# DDR3L.net
KiCad netlist of a schematic drawn in Altium Designer
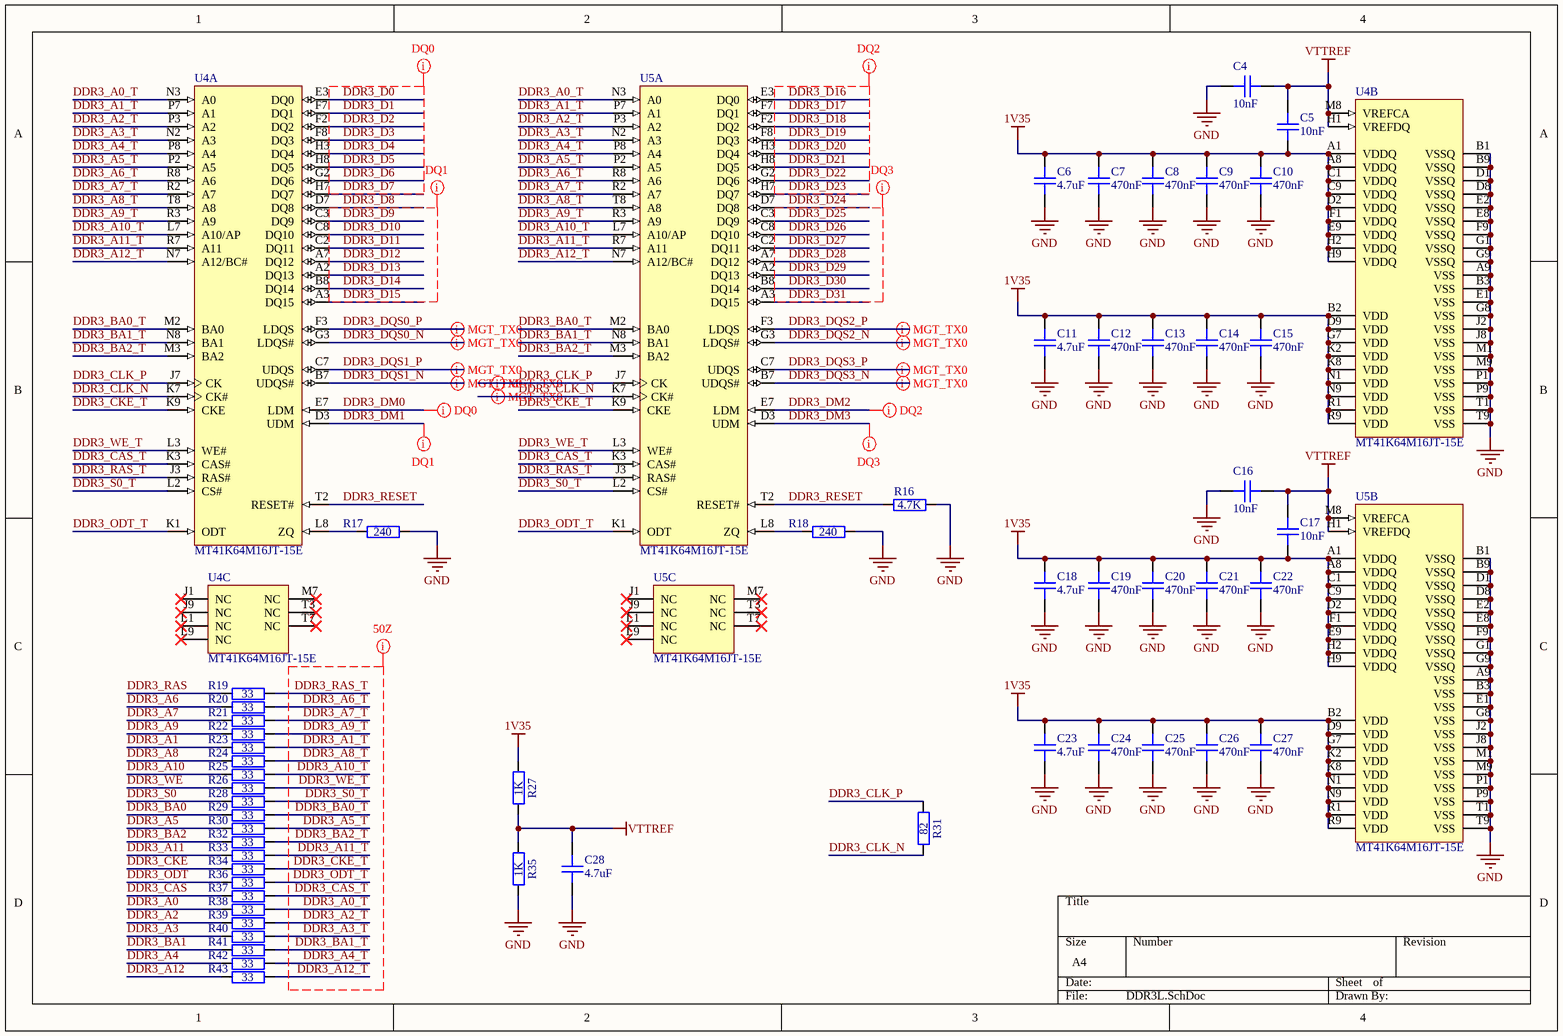
[diagram p0: DDR3L.SchDoc]

(export (version "E")
  (design (tool "Eeschema 10.0.6"))
  (components
    (comp (ref "C4")
      (value "10nF")
      (footprint "GEN_C_0402")
      (libsource (lib "DSO") (part "CAP 10nF 50V X7R 0402"))
    )
    (comp (ref "C5")
      (value "10nF")
      (footprint "GEN_C_0402")
      (libsource (lib "DSO") (part "CAP 10nF 50V X7R 0402"))
    )
    (comp (ref "C6")
      (value "4.7uF")
      (footprint "GEN_C_0402")
      (libsource (lib "DSO") (part "CAP 4.7uF 6.3V X5R 0402"))
    )
    (comp (ref "C7")
      (value "470nF")
      (footprint "GEN_C_0201")
      (libsource (lib "DSO") (part "CAP 470nF 6.3V X5R 0201"))
    )
    (comp (ref "C8")
      (value "470nF")
      (footprint "GEN_C_0201")
      (libsource (lib "DSO") (part "CAP 470nF 6.3V X5R 0201"))
    )
    (comp (ref "C9")
      (value "470nF")
      (footprint "GEN_C_0201")
      (libsource (lib "DSO") (part "CAP 470nF 6.3V X5R 0201"))
    )
    (comp (ref "C10")
      (value "470nF")
      (footprint "GEN_C_0201")
      (libsource (lib "DSO") (part "CAP 470nF 6.3V X5R 0201"))
    )
    (comp (ref "C11")
      (value "4.7uF")
      (footprint "GEN_C_0402")
      (libsource (lib "DSO") (part "CAP 4.7uF 6.3V X5R 0402"))
    )
    (comp (ref "C12")
      (value "470nF")
      (footprint "GEN_C_0201")
      (libsource (lib "DSO") (part "CAP 470nF 6.3V X5R 0201"))
    )
    (comp (ref "C13")
      (value "470nF")
      (footprint "GEN_C_0201")
      (libsource (lib "DSO") (part "CAP 470nF 6.3V X5R 0201"))
    )
    (comp (ref "C14")
      (value "470nF")
      (footprint "GEN_C_0201")
      (libsource (lib "DSO") (part "CAP 470nF 6.3V X5R 0201"))
    )
    (comp (ref "C15")
      (value "470nF")
      (footprint "GEN_C_0201")
      (libsource (lib "DSO") (part "CAP 470nF 6.3V X5R 0201"))
    )
    (comp (ref "C16")
      (value "10nF")
      (footprint "GEN_C_0402")
      (libsource (lib "DSO") (part "CAP 10nF 50V X7R 0402"))
    )
    (comp (ref "C17")
      (value "10nF")
      (footprint "GEN_C_0402")
      (libsource (lib "DSO") (part "CAP 10nF 50V X7R 0402"))
    )
    (comp (ref "C18")
      (value "4.7uF")
      (footprint "GEN_C_0402")
      (libsource (lib "DSO") (part "CAP 4.7uF 6.3V X5R 0402"))
    )
    (comp (ref "C19")
      (value "470nF")
      (footprint "GEN_C_0201")
      (libsource (lib "DSO") (part "CAP 470nF 6.3V X5R 0201"))
    )
    (comp (ref "C20")
      (value "470nF")
      (footprint "GEN_C_0201")
      (libsource (lib "DSO") (part "CAP 470nF 6.3V X5R 0201"))
    )
    (comp (ref "C21")
      (value "470nF")
      (footprint "GEN_C_0201")
      (libsource (lib "DSO") (part "CAP 470nF 6.3V X5R 0201"))
    )
    (comp (ref "C22")
      (value "470nF")
      (footprint "GEN_C_0201")
      (libsource (lib "DSO") (part "CAP 470nF 6.3V X5R 0201"))
    )
    (comp (ref "C23")
      (value "4.7uF")
      (footprint "GEN_C_0402")
      (libsource (lib "DSO") (part "CAP 4.7uF 6.3V X5R 0402"))
    )
    (comp (ref "C24")
      (value "470nF")
      (footprint "GEN_C_0201")
      (libsource (lib "DSO") (part "CAP 470nF 6.3V X5R 0201"))
    )
    (comp (ref "C25")
      (value "470nF")
      (footprint "GEN_C_0201")
      (libsource (lib "DSO") (part "CAP 470nF 6.3V X5R 0201"))
    )
    (comp (ref "C26")
      (value "470nF")
      (footprint "GEN_C_0201")
      (libsource (lib "DSO") (part "CAP 470nF 6.3V X5R 0201"))
    )
    (comp (ref "C27")
      (value "470nF")
      (footprint "GEN_C_0201")
      (libsource (lib "DSO") (part "CAP 470nF 6.3V X5R 0201"))
    )
    (comp (ref "C28")
      (value "4.7uF")
      (footprint "GEN_C_0402")
      (libsource (lib "DSO") (part "CAP 4.7uF 6.3V X5R 0402"))
    )
    (comp (ref "R16")
      (value "4.7K")
      (footprint "GEN_R_0402")
      (fields (field (name "TOLERANCE") "1%"))
      (libsource (lib "DSO") (part "RES 4.7K OHM 1% 1/10W 0402"))
    )
    (comp (ref "R17")
      (value "240")
      (footprint "GEN_R_0402")
      (fields (field (name "TOLERANCE") "1%"))
      (libsource (lib "DSO") (part "RES 240 OHM 1% 1/16W 0402"))
    )
    (comp (ref "R18")
      (value "240")
      (footprint "GEN_R_0402")
      (fields (field (name "TOLERANCE") "1%"))
      (libsource (lib "DSO") (part "RES 240 OHM 1% 1/16W 0402"))
    )
    (comp (ref "R19")
      (value "33")
      (footprint "GEN_R_0201")
      (fields (field (name "TOLERANCE") "1%"))
      (libsource (lib "DSO") (part "RES 33 OHM 1% 1/20W 0201"))
    )
    (comp (ref "R20")
      (value "33")
      (footprint "GEN_R_0201")
      (fields (field (name "TOLERANCE") "1%"))
      (libsource (lib "DSO") (part "RES 33 OHM 1% 1/20W 0201"))
    )
    (comp (ref "R21")
      (value "33")
      (footprint "GEN_R_0201")
      (fields (field (name "TOLERANCE") "1%"))
      (libsource (lib "DSO") (part "RES 33 OHM 1% 1/20W 0201"))
    )
    (comp (ref "R22")
      (value "33")
      (footprint "GEN_R_0201")
      (fields (field (name "TOLERANCE") "1%"))
      (libsource (lib "DSO") (part "RES 33 OHM 1% 1/20W 0201"))
    )
    (comp (ref "R23")
      (value "33")
      (footprint "GEN_R_0201")
      (fields (field (name "TOLERANCE") "1%"))
      (libsource (lib "DSO") (part "RES 33 OHM 1% 1/20W 0201"))
    )
    (comp (ref "R24")
      (value "33")
      (footprint "GEN_R_0201")
      (fields (field (name "TOLERANCE") "1%"))
      (libsource (lib "DSO") (part "RES 33 OHM 1% 1/20W 0201"))
    )
    (comp (ref "R25")
      (value "33")
      (footprint "GEN_R_0201")
      (fields (field (name "TOLERANCE") "1%"))
      (libsource (lib "DSO") (part "RES 33 OHM 1% 1/20W 0201"))
    )
    (comp (ref "R26")
      (value "33")
      (footprint "GEN_R_0201")
      (fields (field (name "TOLERANCE") "1%"))
      (libsource (lib "DSO") (part "RES 33 OHM 1% 1/20W 0201"))
    )
    (comp (ref "R27")
      (value "1K")
      (footprint "GEN_R_0402")
      (fields (field (name "TOLERANCE") "1%"))
      (libsource (lib "DSO") (part "RES 1K OHM 1% 1/10W 0402"))
    )
    (comp (ref "R28")
      (value "33")
      (footprint "GEN_R_0201")
      (fields (field (name "TOLERANCE") "1%"))
      (libsource (lib "DSO") (part "RES 33 OHM 1% 1/20W 0201"))
    )
    (comp (ref "R29")
      (value "33")
      (footprint "GEN_R_0201")
      (fields (field (name "TOLERANCE") "1%"))
      (libsource (lib "DSO") (part "RES 33 OHM 1% 1/20W 0201"))
    )
    (comp (ref "R30")
      (value "33")
      (footprint "GEN_R_0201")
      (fields (field (name "TOLERANCE") "1%"))
      (libsource (lib "DSO") (part "RES 33 OHM 1% 1/20W 0201"))
    )
    (comp (ref "R31")
      (value "82")
      (footprint "GEN_R_0402")
      (fields (field (name "TOLERANCE") "1%"))
      (libsource (lib "DSO") (part "RES 82 OHM 1% 1/16W 0402"))
    )
    (comp (ref "R32")
      (value "33")
      (footprint "GEN_R_0201")
      (fields (field (name "TOLERANCE") "1%"))
      (libsource (lib "DSO") (part "RES 33 OHM 1% 1/20W 0201"))
    )
    (comp (ref "R33")
      (value "33")
      (footprint "GEN_R_0201")
      (fields (field (name "TOLERANCE") "1%"))
      (libsource (lib "DSO") (part "RES 33 OHM 1% 1/20W 0201"))
    )
    (comp (ref "R34")
      (value "33")
      (footprint "GEN_R_0201")
      (fields (field (name "TOLERANCE") "1%"))
      (libsource (lib "DSO") (part "RES 33 OHM 1% 1/20W 0201"))
    )
    (comp (ref "R35")
      (value "1K")
      (footprint "GEN_R_0402")
      (fields (field (name "TOLERANCE") "1%"))
      (libsource (lib "DSO") (part "RES 1K OHM 1% 1/10W 0402"))
    )
    (comp (ref "R36")
      (value "33")
      (footprint "GEN_R_0201")
      (fields (field (name "TOLERANCE") "1%"))
      (libsource (lib "DSO") (part "RES 33 OHM 1% 1/20W 0201"))
    )
    (comp (ref "R37")
      (value "33")
      (footprint "GEN_R_0201")
      (fields (field (name "TOLERANCE") "1%"))
      (libsource (lib "DSO") (part "RES 33 OHM 1% 1/20W 0201"))
    )
    (comp (ref "R38")
      (value "33")
      (footprint "GEN_R_0201")
      (fields (field (name "TOLERANCE") "1%"))
      (libsource (lib "DSO") (part "RES 33 OHM 1% 1/20W 0201"))
    )
    (comp (ref "R39")
      (value "33")
      (footprint "GEN_R_0201")
      (fields (field (name "TOLERANCE") "1%"))
      (libsource (lib "DSO") (part "RES 33 OHM 1% 1/20W 0201"))
    )
    (comp (ref "R40")
      (value "33")
      (footprint "GEN_R_0201")
      (fields (field (name "TOLERANCE") "1%"))
      (libsource (lib "DSO") (part "RES 33 OHM 1% 1/20W 0201"))
    )
    (comp (ref "R41")
      (value "33")
      (footprint "GEN_R_0201")
      (fields (field (name "TOLERANCE") "1%"))
      (libsource (lib "DSO") (part "RES 33 OHM 1% 1/20W 0201"))
    )
    (comp (ref "R42")
      (value "33")
      (footprint "GEN_R_0201")
      (fields (field (name "TOLERANCE") "1%"))
      (libsource (lib "DSO") (part "RES 33 OHM 1% 1/20W 0201"))
    )
    (comp (ref "R43")
      (value "33")
      (footprint "GEN_R_0201")
      (fields (field (name "TOLERANCE") "1%"))
      (libsource (lib "DSO") (part "RES 33 OHM 1% 1/20W 0201"))
    )
    (comp (ref "U4")
      (value "MT41K64M16JT-15E")
      (footprint "MICT-JT-96")
      (description "1Gb DDR3-1333 SDRAM, 64Mb x 16, 1.5ns, 1.35V, 0 to 95 degC, 96-Ball FBGA, Pb-Free")
      (fields (field (name "VOLTAGE") "1.35V") (field (name "MANUFACTURER") "Micron"))
      (libsource (lib "Micron Memory DDR3 SDRAM") (part "MT41K64M16JT-15E"))
    )
    (comp (ref "U5")
      (value "MT41K64M16JT-15E")
      (footprint "MICT-JT-96")
      (description "1Gb DDR3-1333 SDRAM, 64Mb x 16, 1.5ns, 1.35V, 0 to 95 degC, 96-Ball FBGA, Pb-Free")
      (fields (field (name "VOLTAGE") "1.35V") (field (name "MANUFACTURER") "Micron"))
      (libsource (lib "Micron Memory DDR3 SDRAM") (part "MT41K64M16JT-15E"))
    )
  )
  (nets
    (net (code "1") (name "/DDR3_A0") (class "Default")
      (node (ref "R38") (pin "1") (pinfunction "1_1") (pintype "passive"))
    )
    (net (code "2") (name "/DDR3_A0_T") (class "Default")
      (node (ref "R38") (pin "2") (pinfunction "2_2") (pintype "passive"))
      (node (ref "U4") (pin "N3") (pinfunction "A0_N3") (pintype "input"))
      (node (ref "U5") (pin "N3") (pinfunction "A0_N3") (pintype "input"))
    )
    (net (code "3") (name "/DDR3_A1") (class "Default")
      (node (ref "R23") (pin "1") (pinfunction "1_1") (pintype "passive"))
    )
    (net (code "4") (name "/DDR3_A1_T") (class "Default")
      (node (ref "R23") (pin "2") (pinfunction "2_2") (pintype "passive"))
      (node (ref "U4") (pin "P7") (pinfunction "A1_P7") (pintype "input"))
      (node (ref "U5") (pin "P7") (pinfunction "A1_P7") (pintype "input"))
    )
    (net (code "5") (name "/DDR3_A2") (class "Default")
      (node (ref "R39") (pin "1") (pinfunction "1_1") (pintype "passive"))
    )
    (net (code "6") (name "/DDR3_A2_T") (class "Default")
      (node (ref "R39") (pin "2") (pinfunction "2_2") (pintype "passive"))
      (node (ref "U4") (pin "P3") (pinfunction "A2_P3") (pintype "input"))
      (node (ref "U5") (pin "P3") (pinfunction "A2_P3") (pintype "input"))
    )
    (net (code "7") (name "/DDR3_A3") (class "Default")
      (node (ref "R40") (pin "1") (pinfunction "1_1") (pintype "passive"))
    )
    (net (code "8") (name "/DDR3_A3_T") (class "Default")
      (node (ref "R40") (pin "2") (pinfunction "2_2") (pintype "passive"))
      (node (ref "U4") (pin "N2") (pinfunction "A3_N2") (pintype "input"))
      (node (ref "U5") (pin "N2") (pinfunction "A3_N2") (pintype "input"))
    )
    (net (code "9") (name "/DDR3_A4") (class "Default")
      (node (ref "R42") (pin "1") (pinfunction "1_1") (pintype "passive"))
    )
    (net (code "10") (name "/DDR3_A4_T") (class "Default")
      (node (ref "R42") (pin "2") (pinfunction "2_2") (pintype "passive"))
      (node (ref "U4") (pin "P8") (pinfunction "A4_P8") (pintype "input"))
      (node (ref "U5") (pin "P8") (pinfunction "A4_P8") (pintype "input"))
    )
    (net (code "11") (name "/DDR3_A5") (class "Default")
      (node (ref "R30") (pin "1") (pinfunction "1_1") (pintype "passive"))
    )
    (net (code "12") (name "/DDR3_A5_T") (class "Default")
      (node (ref "R30") (pin "2") (pinfunction "2_2") (pintype "passive"))
      (node (ref "U4") (pin "P2") (pinfunction "A5_P2") (pintype "input"))
      (node (ref "U5") (pin "P2") (pinfunction "A5_P2") (pintype "input"))
    )
    (net (code "13") (name "/DDR3_A6") (class "Default")
      (node (ref "R20") (pin "1") (pinfunction "1_1") (pintype "passive"))
    )
    (net (code "14") (name "/DDR3_A6_T") (class "Default")
      (node (ref "R20") (pin "2") (pinfunction "2_2") (pintype "passive"))
      (node (ref "U4") (pin "R8") (pinfunction "A6_R8") (pintype "input"))
      (node (ref "U5") (pin "R8") (pinfunction "A6_R8") (pintype "input"))
    )
    (net (code "15") (name "/DDR3_A7") (class "Default")
      (node (ref "R21") (pin "1") (pinfunction "1_1") (pintype "passive"))
    )
    (net (code "16") (name "/DDR3_A7_T") (class "Default")
      (node (ref "R21") (pin "2") (pinfunction "2_2") (pintype "passive"))
      (node (ref "U4") (pin "R2") (pinfunction "A7_R2") (pintype "input"))
      (node (ref "U5") (pin "R2") (pinfunction "A7_R2") (pintype "input"))
    )
    (net (code "17") (name "/DDR3_A8") (class "Default")
      (node (ref "R24") (pin "1") (pinfunction "1_1") (pintype "passive"))
    )
    (net (code "18") (name "/DDR3_A8_T") (class "Default")
      (node (ref "R24") (pin "2") (pinfunction "2_2") (pintype "passive"))
      (node (ref "U4") (pin "T8") (pinfunction "A8_T8") (pintype "input"))
      (node (ref "U5") (pin "T8") (pinfunction "A8_T8") (pintype "input"))
    )
    (net (code "19") (name "/DDR3_A9") (class "Default")
      (node (ref "R22") (pin "1") (pinfunction "1_1") (pintype "passive"))
    )
    (net (code "20") (name "/DDR3_A9_T") (class "Default")
      (node (ref "R22") (pin "2") (pinfunction "2_2") (pintype "passive"))
      (node (ref "U4") (pin "R3") (pinfunction "A9_R3") (pintype "input"))
      (node (ref "U5") (pin "R3") (pinfunction "A9_R3") (pintype "input"))
    )
    (net (code "21") (name "/DDR3_A10") (class "Default")
      (node (ref "R25") (pin "1") (pinfunction "1_1") (pintype "passive"))
    )
    (net (code "22") (name "/DDR3_A10_T") (class "Default")
      (node (ref "R25") (pin "2") (pinfunction "2_2") (pintype "passive"))
      (node (ref "U4") (pin "L7") (pinfunction "A10/AP_L7") (pintype "input"))
      (node (ref "U5") (pin "L7") (pinfunction "A10/AP_L7") (pintype "input"))
    )
    (net (code "23") (name "/DDR3_A11") (class "Default")
      (node (ref "R33") (pin "1") (pinfunction "1_1") (pintype "passive"))
    )
    (net (code "24") (name "/DDR3_A11_T") (class "Default")
      (node (ref "R33") (pin "2") (pinfunction "2_2") (pintype "passive"))
      (node (ref "U4") (pin "R7") (pinfunction "A11_R7") (pintype "input"))
      (node (ref "U5") (pin "R7") (pinfunction "A11_R7") (pintype "input"))
    )
    (net (code "25") (name "/DDR3_A12") (class "Default")
      (node (ref "R43") (pin "1") (pinfunction "1_1") (pintype "passive"))
    )
    (net (code "26") (name "/DDR3_A12_T") (class "Default")
      (node (ref "R43") (pin "2") (pinfunction "2_2") (pintype "passive"))
      (node (ref "U4") (pin "N7") (pinfunction "A12/BC#_N7") (pintype "input"))
      (node (ref "U5") (pin "N7") (pinfunction "A12/BC#_N7") (pintype "input"))
    )
    (net (code "27") (name "/DDR3_BA0") (class "Default")
      (node (ref "R29") (pin "1") (pinfunction "1_1") (pintype "passive"))
    )
    (net (code "28") (name "/DDR3_BA0_T") (class "Default")
      (node (ref "R29") (pin "2") (pinfunction "2_2") (pintype "passive"))
      (node (ref "U4") (pin "M2") (pinfunction "BA0_M2") (pintype "input"))
      (node (ref "U5") (pin "M2") (pinfunction "BA0_M2") (pintype "input"))
    )
    (net (code "29") (name "/DDR3_BA1") (class "Default")
      (node (ref "R41") (pin "1") (pinfunction "1_1") (pintype "passive"))
    )
    (net (code "30") (name "/DDR3_BA1_T") (class "Default")
      (node (ref "R41") (pin "2") (pinfunction "2_2") (pintype "passive"))
      (node (ref "U4") (pin "N8") (pinfunction "BA1_N8") (pintype "input"))
      (node (ref "U5") (pin "N8") (pinfunction "BA1_N8") (pintype "input"))
    )
    (net (code "31") (name "/DDR3_BA2") (class "Default")
      (node (ref "R32") (pin "1") (pinfunction "1_1") (pintype "passive"))
    )
    (net (code "32") (name "/DDR3_BA2_T") (class "Default")
      (node (ref "R32") (pin "2") (pinfunction "2_2") (pintype "passive"))
      (node (ref "U4") (pin "M3") (pinfunction "BA2_M3") (pintype "input"))
      (node (ref "U5") (pin "M3") (pinfunction "BA2_M3") (pintype "input"))
    )
    (net (code "33") (name "/DDR3_CAS") (class "Default")
      (node (ref "R37") (pin "1") (pinfunction "1_1") (pintype "passive"))
    )
    (net (code "34") (name "/DDR3_CAS_T") (class "Default")
      (node (ref "R37") (pin "2") (pinfunction "2_2") (pintype "passive"))
      (node (ref "U4") (pin "K3") (pinfunction "CAS#_K3") (pintype "input"))
      (node (ref "U5") (pin "K3") (pinfunction "CAS#_K3") (pintype "input"))
    )
    (net (code "35") (name "/DDR3_CKE") (class "Default")
      (node (ref "R34") (pin "1") (pinfunction "1_1") (pintype "passive"))
    )
    (net (code "36") (name "/DDR3_CKE_T") (class "Default")
      (node (ref "R34") (pin "2") (pinfunction "2_2") (pintype "passive"))
      (node (ref "U4") (pin "K9") (pinfunction "CKE_K9") (pintype "input"))
      (node (ref "U5") (pin "K9") (pinfunction "CKE_K9") (pintype "input"))
    )
    (net (code "37") (name "/DDR3_CLK_N") (class "Default")
      (node (ref "R31") (pin "1") (pinfunction "1_1") (pintype "passive"))
      (node (ref "U4") (pin "K7") (pinfunction "CK#_K7") (pintype "input"))
      (node (ref "U5") (pin "K7") (pinfunction "CK#_K7") (pintype "input"))
    )
    (net (code "38") (name "/DDR3_CLK_P") (class "Default")
      (node (ref "R31") (pin "2") (pinfunction "2_2") (pintype "passive"))
      (node (ref "U4") (pin "J7") (pinfunction "CK_J7") (pintype "input"))
      (node (ref "U5") (pin "J7") (pinfunction "CK_J7") (pintype "input"))
    )
    (net (code "39") (name "/DDR3_D0") (class "Default")
      (node (ref "U4") (pin "E3") (pinfunction "DQ0_E3") (pintype "bidirectional"))
    )
    (net (code "40") (name "/DDR3_D1") (class "Default")
      (node (ref "U4") (pin "F7") (pinfunction "DQ1_F7") (pintype "bidirectional"))
    )
    (net (code "41") (name "/DDR3_D2") (class "Default")
      (node (ref "U4") (pin "F2") (pinfunction "DQ2_F2") (pintype "bidirectional"))
    )
    (net (code "42") (name "/DDR3_D3") (class "Default")
      (node (ref "U4") (pin "F8") (pinfunction "DQ3_F8") (pintype "bidirectional"))
    )
    (net (code "43") (name "/DDR3_D4") (class "Default")
      (node (ref "U4") (pin "H3") (pinfunction "DQ4_H3") (pintype "bidirectional"))
    )
    (net (code "44") (name "/DDR3_D5") (class "Default")
      (node (ref "U4") (pin "H8") (pinfunction "DQ5_H8") (pintype "bidirectional"))
    )
    (net (code "45") (name "/DDR3_D6") (class "Default")
      (node (ref "U4") (pin "G2") (pinfunction "DQ6_G2") (pintype "bidirectional"))
    )
    (net (code "46") (name "/DDR3_D7") (class "Default")
      (node (ref "U4") (pin "H7") (pinfunction "DQ7_H7") (pintype "bidirectional"))
    )
    (net (code "47") (name "/DDR3_D8") (class "Default")
      (node (ref "U4") (pin "D7") (pinfunction "DQ8_D7") (pintype "bidirectional"))
    )
    (net (code "48") (name "/DDR3_D9") (class "Default")
      (node (ref "U4") (pin "C3") (pinfunction "DQ9_C3") (pintype "bidirectional"))
    )
    (net (code "49") (name "/DDR3_D10") (class "Default")
      (node (ref "U4") (pin "C8") (pinfunction "DQ10_C8") (pintype "bidirectional"))
    )
    (net (code "50") (name "/DDR3_D11") (class "Default")
      (node (ref "U4") (pin "C2") (pinfunction "DQ11_C2") (pintype "bidirectional"))
    )
    (net (code "51") (name "/DDR3_D12") (class "Default")
      (node (ref "U4") (pin "A7") (pinfunction "DQ12_A7") (pintype "bidirectional"))
    )
    (net (code "52") (name "/DDR3_D13") (class "Default")
      (node (ref "U4") (pin "A2") (pinfunction "DQ13_A2") (pintype "bidirectional"))
    )
    (net (code "53") (name "/DDR3_D14") (class "Default")
      (node (ref "U4") (pin "B8") (pinfunction "DQ14_B8") (pintype "bidirectional"))
    )
    (net (code "54") (name "/DDR3_D15") (class "Default")
      (node (ref "U4") (pin "A3") (pinfunction "DQ15_A3") (pintype "bidirectional"))
    )
    (net (code "55") (name "/DDR3_D16") (class "Default")
      (node (ref "U5") (pin "E3") (pinfunction "DQ0_E3") (pintype "bidirectional"))
    )
    (net (code "56") (name "/DDR3_D17") (class "Default")
      (node (ref "U5") (pin "F7") (pinfunction "DQ1_F7") (pintype "bidirectional"))
    )
    (net (code "57") (name "/DDR3_D18") (class "Default")
      (node (ref "U5") (pin "F2") (pinfunction "DQ2_F2") (pintype "bidirectional"))
    )
    (net (code "58") (name "/DDR3_D19") (class "Default")
      (node (ref "U5") (pin "F8") (pinfunction "DQ3_F8") (pintype "bidirectional"))
    )
    (net (code "59") (name "/DDR3_D20") (class "Default")
      (node (ref "U5") (pin "H3") (pinfunction "DQ4_H3") (pintype "bidirectional"))
    )
    (net (code "60") (name "/DDR3_D21") (class "Default")
      (node (ref "U5") (pin "H8") (pinfunction "DQ5_H8") (pintype "bidirectional"))
    )
    (net (code "61") (name "/DDR3_D22") (class "Default")
      (node (ref "U5") (pin "G2") (pinfunction "DQ6_G2") (pintype "bidirectional"))
    )
    (net (code "62") (name "/DDR3_D23") (class "Default")
      (node (ref "U5") (pin "H7") (pinfunction "DQ7_H7") (pintype "bidirectional"))
    )
    (net (code "63") (name "/DDR3_D24") (class "Default")
      (node (ref "U5") (pin "D7") (pinfunction "DQ8_D7") (pintype "bidirectional"))
    )
    (net (code "64") (name "/DDR3_D25") (class "Default")
      (node (ref "U5") (pin "C3") (pinfunction "DQ9_C3") (pintype "bidirectional"))
    )
    (net (code "65") (name "/DDR3_D26") (class "Default")
      (node (ref "U5") (pin "C8") (pinfunction "DQ10_C8") (pintype "bidirectional"))
    )
    (net (code "66") (name "/DDR3_D27") (class "Default")
      (node (ref "U5") (pin "C2") (pinfunction "DQ11_C2") (pintype "bidirectional"))
    )
    (net (code "67") (name "/DDR3_D28") (class "Default")
      (node (ref "U5") (pin "A7") (pinfunction "DQ12_A7") (pintype "bidirectional"))
    )
    (net (code "68") (name "/DDR3_D29") (class "Default")
      (node (ref "U5") (pin "A2") (pinfunction "DQ13_A2") (pintype "bidirectional"))
    )
    (net (code "69") (name "/DDR3_D30") (class "Default")
      (node (ref "U5") (pin "B8") (pinfunction "DQ14_B8") (pintype "bidirectional"))
    )
    (net (code "70") (name "/DDR3_D31") (class "Default")
      (node (ref "U5") (pin "A3") (pinfunction "DQ15_A3") (pintype "bidirectional"))
    )
    (net (code "71") (name "/DDR3_DM0") (class "Default")
      (node (ref "U4") (pin "E7") (pinfunction "LDM_E7") (pintype "input"))
    )
    (net (code "72") (name "/DDR3_DM1") (class "Default")
      (node (ref "U4") (pin "D3") (pinfunction "UDM_D3") (pintype "input"))
    )
    (net (code "73") (name "/DDR3_DM2") (class "Default")
      (node (ref "U5") (pin "E7") (pinfunction "LDM_E7") (pintype "input"))
    )
    (net (code "74") (name "/DDR3_DM3") (class "Default")
      (node (ref "U5") (pin "D3") (pinfunction "UDM_D3") (pintype "input"))
    )
    (net (code "75") (name "/DDR3_DQS0_N") (class "Default")
      (node (ref "U4") (pin "G3") (pinfunction "LDQS#_G3") (pintype "bidirectional"))
    )
    (net (code "76") (name "/DDR3_DQS0_P") (class "Default")
      (node (ref "U4") (pin "F3") (pinfunction "LDQS_F3") (pintype "bidirectional"))
    )
    (net (code "77") (name "/DDR3_DQS1_N") (class "Default")
      (node (ref "U4") (pin "B7") (pinfunction "UDQS#_B7") (pintype "bidirectional"))
    )
    (net (code "78") (name "/DDR3_DQS1_P") (class "Default")
      (node (ref "U4") (pin "C7") (pinfunction "UDQS_C7") (pintype "bidirectional"))
    )
    (net (code "79") (name "/DDR3_DQS2_N") (class "Default")
      (node (ref "U5") (pin "G3") (pinfunction "LDQS#_G3") (pintype "bidirectional"))
    )
    (net (code "80") (name "/DDR3_DQS2_P") (class "Default")
      (node (ref "U5") (pin "F3") (pinfunction "LDQS_F3") (pintype "bidirectional"))
    )
    (net (code "81") (name "/DDR3_DQS3_N") (class "Default")
      (node (ref "U5") (pin "B7") (pinfunction "UDQS#_B7") (pintype "bidirectional"))
    )
    (net (code "82") (name "/DDR3_DQS3_P") (class "Default")
      (node (ref "U5") (pin "C7") (pinfunction "UDQS_C7") (pintype "bidirectional"))
    )
    (net (code "83") (name "/DDR3_ODT") (class "Default")
      (node (ref "R36") (pin "1") (pinfunction "1_1") (pintype "passive"))
    )
    (net (code "84") (name "/DDR3_ODT_T") (class "Default")
      (node (ref "R36") (pin "2") (pinfunction "2_2") (pintype "passive"))
      (node (ref "U4") (pin "K1") (pinfunction "ODT_K1") (pintype "input"))
      (node (ref "U5") (pin "K1") (pinfunction "ODT_K1") (pintype "input"))
    )
    (net (code "85") (name "/DDR3_RAS") (class "Default")
      (node (ref "R19") (pin "1") (pinfunction "1_1") (pintype "passive"))
    )
    (net (code "86") (name "/DDR3_RAS_T") (class "Default")
      (node (ref "R19") (pin "2") (pinfunction "2_2") (pintype "passive"))
      (node (ref "U4") (pin "J3") (pinfunction "RAS#_J3") (pintype "input"))
      (node (ref "U5") (pin "J3") (pinfunction "RAS#_J3") (pintype "input"))
    )
    (net (code "87") (name "/DDR3_RESET") (class "Default")
      (node (ref "R16") (pin "1") (pinfunction "1_1") (pintype "passive"))
      (node (ref "U4") (pin "T2") (pinfunction "RESET#_T2") (pintype "input"))
      (node (ref "U5") (pin "T2") (pinfunction "RESET#_T2") (pintype "input"))
    )
    (net (code "88") (name "/DDR3_S0") (class "Default")
      (node (ref "R28") (pin "1") (pinfunction "1_1") (pintype "passive"))
    )
    (net (code "89") (name "/DDR3_S0_T") (class "Default")
      (node (ref "R28") (pin "2") (pinfunction "2_2") (pintype "passive"))
      (node (ref "U4") (pin "L2") (pinfunction "CS#_L2") (pintype "input"))
      (node (ref "U5") (pin "L2") (pinfunction "CS#_L2") (pintype "input"))
    )
    (net (code "90") (name "/DDR3_WE") (class "Default")
      (node (ref "R26") (pin "1") (pinfunction "1_1") (pintype "passive"))
    )
    (net (code "91") (name "/DDR3_WE_T") (class "Default")
      (node (ref "R26") (pin "2") (pinfunction "2_2") (pintype "passive"))
      (node (ref "U4") (pin "L3") (pinfunction "WE#_L3") (pintype "input"))
      (node (ref "U5") (pin "L3") (pinfunction "WE#_L3") (pintype "input"))
    )
    (net (code "92") (name "1V35") (class "Default")
      (node (ref "C10") (pin "2") (pinfunction "2_2") (pintype "passive"))
      (node (ref "C11") (pin "2") (pinfunction "2_2") (pintype "passive"))
      (node (ref "C12") (pin "2") (pinfunction "2_2") (pintype "passive"))
      (node (ref "C13") (pin "2") (pinfunction "2_2") (pintype "passive"))
      (node (ref "C14") (pin "2") (pinfunction "2_2") (pintype "passive"))
      (node (ref "C15") (pin "2") (pinfunction "2_2") (pintype "passive"))
      (node (ref "C17") (pin "2") (pinfunction "2_2") (pintype "passive"))
      (node (ref "C18") (pin "2") (pinfunction "2_2") (pintype "passive"))
      (node (ref "C19") (pin "2") (pinfunction "2_2") (pintype "passive"))
      (node (ref "C20") (pin "2") (pinfunction "2_2") (pintype "passive"))
      (node (ref "C21") (pin "2") (pinfunction "2_2") (pintype "passive"))
      (node (ref "C22") (pin "2") (pinfunction "2_2") (pintype "passive"))
      (node (ref "C23") (pin "2") (pinfunction "2_2") (pintype "passive"))
      (node (ref "C24") (pin "2") (pinfunction "2_2") (pintype "passive"))
      (node (ref "C25") (pin "2") (pinfunction "2_2") (pintype "passive"))
      (node (ref "C26") (pin "2") (pinfunction "2_2") (pintype "passive"))
      (node (ref "C27") (pin "2") (pinfunction "2_2") (pintype "passive"))
      (node (ref "C5") (pin "2") (pinfunction "2_2") (pintype "passive"))
      (node (ref "C6") (pin "2") (pinfunction "2_2") (pintype "passive"))
      (node (ref "C7") (pin "2") (pinfunction "2_2") (pintype "passive"))
      (node (ref "C8") (pin "2") (pinfunction "2_2") (pintype "passive"))
      (node (ref "C9") (pin "2") (pinfunction "2_2") (pintype "passive"))
      (node (ref "R27") (pin "2") (pinfunction "2_2") (pintype "passive"))
      (node (ref "U4") (pin "A1") (pinfunction "VDDQ_A1") (pintype "power_in"))
      (node (ref "U4") (pin "A8") (pinfunction "VDDQ_A8") (pintype "power_in"))
      (node (ref "U4") (pin "B2") (pinfunction "VDD_B2") (pintype "power_in"))
      (node (ref "U4") (pin "C1") (pinfunction "VDDQ_C1") (pintype "power_in"))
      (node (ref "U4") (pin "C9") (pinfunction "VDDQ_C9") (pintype "power_in"))
      (node (ref "U4") (pin "D2") (pinfunction "VDDQ_D2") (pintype "power_in"))
      (node (ref "U4") (pin "D9") (pinfunction "VDD_D9") (pintype "power_in"))
      (node (ref "U4") (pin "E9") (pinfunction "VDDQ_E9") (pintype "power_in"))
      (node (ref "U4") (pin "F1") (pinfunction "VDDQ_F1") (pintype "power_in"))
      (node (ref "U4") (pin "G7") (pinfunction "VDD_G7") (pintype "power_in"))
      (node (ref "U4") (pin "H2") (pinfunction "VDDQ_H2") (pintype "power_in"))
      (node (ref "U4") (pin "H9") (pinfunction "VDDQ_H9") (pintype "power_in"))
      (node (ref "U4") (pin "K2") (pinfunction "VDD_K2") (pintype "power_in"))
      (node (ref "U4") (pin "K8") (pinfunction "VDD_K8") (pintype "power_in"))
      (node (ref "U4") (pin "N1") (pinfunction "VDD_N1") (pintype "power_in"))
      (node (ref "U4") (pin "N9") (pinfunction "VDD_N9") (pintype "power_in"))
      (node (ref "U4") (pin "R1") (pinfunction "VDD_R1") (pintype "power_in"))
      (node (ref "U4") (pin "R9") (pinfunction "VDD_R9") (pintype "power_in"))
      (node (ref "U5") (pin "A1") (pinfunction "VDDQ_A1") (pintype "power_in"))
      (node (ref "U5") (pin "A8") (pinfunction "VDDQ_A8") (pintype "power_in"))
      (node (ref "U5") (pin "B2") (pinfunction "VDD_B2") (pintype "power_in"))
      (node (ref "U5") (pin "C1") (pinfunction "VDDQ_C1") (pintype "power_in"))
      (node (ref "U5") (pin "C9") (pinfunction "VDDQ_C9") (pintype "power_in"))
      (node (ref "U5") (pin "D2") (pinfunction "VDDQ_D2") (pintype "power_in"))
      (node (ref "U5") (pin "D9") (pinfunction "VDD_D9") (pintype "power_in"))
      (node (ref "U5") (pin "E9") (pinfunction "VDDQ_E9") (pintype "power_in"))
      (node (ref "U5") (pin "F1") (pinfunction "VDDQ_F1") (pintype "power_in"))
      (node (ref "U5") (pin "G7") (pinfunction "VDD_G7") (pintype "power_in"))
      (node (ref "U5") (pin "H2") (pinfunction "VDDQ_H2") (pintype "power_in"))
      (node (ref "U5") (pin "H9") (pinfunction "VDDQ_H9") (pintype "power_in"))
      (node (ref "U5") (pin "K2") (pinfunction "VDD_K2") (pintype "power_in"))
      (node (ref "U5") (pin "K8") (pinfunction "VDD_K8") (pintype "power_in"))
      (node (ref "U5") (pin "N1") (pinfunction "VDD_N1") (pintype "power_in"))
      (node (ref "U5") (pin "N9") (pinfunction "VDD_N9") (pintype "power_in"))
      (node (ref "U5") (pin "R1") (pinfunction "VDD_R1") (pintype "power_in"))
      (node (ref "U5") (pin "R9") (pinfunction "VDD_R9") (pintype "power_in"))
    )
    (net (code "93") (name "GND") (class "Default")
      (node (ref "C10") (pin "1") (pinfunction "1_1") (pintype "passive"))
      (node (ref "C11") (pin "1") (pinfunction "1_1") (pintype "passive"))
      (node (ref "C12") (pin "1") (pinfunction "1_1") (pintype "passive"))
      (node (ref "C13") (pin "1") (pinfunction "1_1") (pintype "passive"))
      (node (ref "C14") (pin "1") (pinfunction "1_1") (pintype "passive"))
      (node (ref "C15") (pin "1") (pinfunction "1_1") (pintype "passive"))
      (node (ref "C16") (pin "1") (pinfunction "1_1") (pintype "passive"))
      (node (ref "C18") (pin "1") (pinfunction "1_1") (pintype "passive"))
      (node (ref "C19") (pin "1") (pinfunction "1_1") (pintype "passive"))
      (node (ref "C20") (pin "1") (pinfunction "1_1") (pintype "passive"))
      (node (ref "C21") (pin "1") (pinfunction "1_1") (pintype "passive"))
      (node (ref "C22") (pin "1") (pinfunction "1_1") (pintype "passive"))
      (node (ref "C23") (pin "1") (pinfunction "1_1") (pintype "passive"))
      (node (ref "C24") (pin "1") (pinfunction "1_1") (pintype "passive"))
      (node (ref "C25") (pin "1") (pinfunction "1_1") (pintype "passive"))
      (node (ref "C26") (pin "1") (pinfunction "1_1") (pintype "passive"))
      (node (ref "C27") (pin "1") (pinfunction "1_1") (pintype "passive"))
      (node (ref "C28") (pin "1") (pinfunction "1_1") (pintype "passive"))
      (node (ref "C4") (pin "1") (pinfunction "1_1") (pintype "passive"))
      (node (ref "C6") (pin "1") (pinfunction "1_1") (pintype "passive"))
      (node (ref "C7") (pin "1") (pinfunction "1_1") (pintype "passive"))
      (node (ref "C8") (pin "1") (pinfunction "1_1") (pintype "passive"))
      (node (ref "C9") (pin "1") (pinfunction "1_1") (pintype "passive"))
      (node (ref "R16") (pin "2") (pinfunction "2_2") (pintype "passive"))
      (node (ref "R17") (pin "2") (pinfunction "2_2") (pintype "passive"))
      (node (ref "R18") (pin "2") (pinfunction "2_2") (pintype "passive"))
      (node (ref "R35") (pin "1") (pinfunction "1_1") (pintype "passive"))
      (node (ref "U4") (pin "A9") (pinfunction "VSS_A9") (pintype "power_in"))
      (node (ref "U4") (pin "B1") (pinfunction "VSSQ_B1") (pintype "power_in"))
      (node (ref "U4") (pin "B3") (pinfunction "VSS_B3") (pintype "power_in"))
      (node (ref "U4") (pin "B9") (pinfunction "VSSQ_B9") (pintype "power_in"))
      (node (ref "U4") (pin "D1") (pinfunction "VSSQ_D1") (pintype "power_in"))
      (node (ref "U4") (pin "D8") (pinfunction "VSSQ_D8") (pintype "power_in"))
      (node (ref "U4") (pin "E1") (pinfunction "VSS_E1") (pintype "power_in"))
      (node (ref "U4") (pin "E2") (pinfunction "VSSQ_E2") (pintype "power_in"))
      (node (ref "U4") (pin "E8") (pinfunction "VSSQ_E8") (pintype "power_in"))
      (node (ref "U4") (pin "F9") (pinfunction "VSSQ_F9") (pintype "power_in"))
      (node (ref "U4") (pin "G1") (pinfunction "VSSQ_G1") (pintype "power_in"))
      (node (ref "U4") (pin "G8") (pinfunction "VSS_G8") (pintype "power_in"))
      (node (ref "U4") (pin "G9") (pinfunction "VSSQ_G9") (pintype "power_in"))
      (node (ref "U4") (pin "J2") (pinfunction "VSS_J2") (pintype "power_in"))
      (node (ref "U4") (pin "J8") (pinfunction "VSS_J8") (pintype "power_in"))
      (node (ref "U4") (pin "M1") (pinfunction "VSS_M1") (pintype "power_in"))
      (node (ref "U4") (pin "M9") (pinfunction "VSS_M9") (pintype "power_in"))
      (node (ref "U4") (pin "P1") (pinfunction "VSS_P1") (pintype "power_in"))
      (node (ref "U4") (pin "P9") (pinfunction "VSS_P9") (pintype "power_in"))
      (node (ref "U4") (pin "T1") (pinfunction "VSS_T1") (pintype "power_in"))
      (node (ref "U4") (pin "T9") (pinfunction "VSS_T9") (pintype "power_in"))
      (node (ref "U5") (pin "A9") (pinfunction "VSS_A9") (pintype "power_in"))
      (node (ref "U5") (pin "B1") (pinfunction "VSSQ_B1") (pintype "power_in"))
      (node (ref "U5") (pin "B3") (pinfunction "VSS_B3") (pintype "power_in"))
      (node (ref "U5") (pin "B9") (pinfunction "VSSQ_B9") (pintype "power_in"))
      (node (ref "U5") (pin "D1") (pinfunction "VSSQ_D1") (pintype "power_in"))
      (node (ref "U5") (pin "D8") (pinfunction "VSSQ_D8") (pintype "power_in"))
      (node (ref "U5") (pin "E1") (pinfunction "VSS_E1") (pintype "power_in"))
      (node (ref "U5") (pin "E2") (pinfunction "VSSQ_E2") (pintype "power_in"))
      (node (ref "U5") (pin "E8") (pinfunction "VSSQ_E8") (pintype "power_in"))
      (node (ref "U5") (pin "F9") (pinfunction "VSSQ_F9") (pintype "power_in"))
      (node (ref "U5") (pin "G1") (pinfunction "VSSQ_G1") (pintype "power_in"))
      (node (ref "U5") (pin "G8") (pinfunction "VSS_G8") (pintype "power_in"))
      (node (ref "U5") (pin "G9") (pinfunction "VSSQ_G9") (pintype "power_in"))
      (node (ref "U5") (pin "J2") (pinfunction "VSS_J2") (pintype "power_in"))
      (node (ref "U5") (pin "J8") (pinfunction "VSS_J8") (pintype "power_in"))
      (node (ref "U5") (pin "M1") (pinfunction "VSS_M1") (pintype "power_in"))
      (node (ref "U5") (pin "M9") (pinfunction "VSS_M9") (pintype "power_in"))
      (node (ref "U5") (pin "P1") (pinfunction "VSS_P1") (pintype "power_in"))
      (node (ref "U5") (pin "P9") (pinfunction "VSS_P9") (pintype "power_in"))
      (node (ref "U5") (pin "T1") (pinfunction "VSS_T1") (pintype "power_in"))
      (node (ref "U5") (pin "T9") (pinfunction "VSS_T9") (pintype "power_in"))
    )
    (net (code "94") (name "Net-(U4A-ZQ)") (class "Default")
      (node (ref "R17") (pin "1") (pinfunction "1_1") (pintype "passive"))
      (node (ref "U4") (pin "L8") (pinfunction "ZQ_L8") (pintype "input"))
    )
    (net (code "95") (name "Net-(U5A-ZQ)") (class "Default")
      (node (ref "R18") (pin "1") (pinfunction "1_1") (pintype "passive"))
      (node (ref "U5") (pin "L8") (pinfunction "ZQ_L8") (pintype "input"))
    )
    (net (code "96") (name "VTTREF") (class "Default")
      (node (ref "C16") (pin "2") (pinfunction "2_2") (pintype "passive"))
      (node (ref "C17") (pin "1") (pinfunction "1_1") (pintype "passive"))
      (node (ref "C28") (pin "2") (pinfunction "2_2") (pintype "passive"))
      (node (ref "C4") (pin "2") (pinfunction "2_2") (pintype "passive"))
      (node (ref "C5") (pin "1") (pinfunction "1_1") (pintype "passive"))
      (node (ref "R27") (pin "1") (pinfunction "1_1") (pintype "passive"))
      (node (ref "R35") (pin "2") (pinfunction "2_2") (pintype "passive"))
      (node (ref "U4") (pin "H1") (pinfunction "VREFDQ_H1") (pintype "input"))
      (node (ref "U4") (pin "M8") (pinfunction "VREFCA_M8") (pintype "input"))
      (node (ref "U5") (pin "H1") (pinfunction "VREFDQ_H1") (pintype "input"))
      (node (ref "U5") (pin "M8") (pinfunction "VREFCA_M8") (pintype "input"))
    )
    (net (code "97") (name "unconnected-(U4C-NC-PadJ1)") (class "Default")
      (node (ref "U4") (pin "J1") (pinfunction "NC_J1") (pintype "passive+no_connect"))
    )
    (net (code "98") (name "unconnected-(U4C-NC-PadJ9)") (class "Default")
      (node (ref "U4") (pin "J9") (pinfunction "NC_J9") (pintype "passive+no_connect"))
    )
    (net (code "99") (name "unconnected-(U4C-NC-PadL1)") (class "Default")
      (node (ref "U4") (pin "L1") (pinfunction "NC_L1") (pintype "passive+no_connect"))
    )
    (net (code "100") (name "unconnected-(U4C-NC-PadL9)") (class "Default")
      (node (ref "U4") (pin "L9") (pinfunction "NC_L9") (pintype "passive+no_connect"))
    )
    (net (code "101") (name "unconnected-(U4C-NC-PadM7)") (class "Default")
      (node (ref "U4") (pin "M7") (pinfunction "NC_M7") (pintype "passive+no_connect"))
    )
    (net (code "102") (name "unconnected-(U4C-NC-PadT3)") (class "Default")
      (node (ref "U4") (pin "T3") (pinfunction "NC_T3") (pintype "passive+no_connect"))
    )
    (net (code "103") (name "unconnected-(U4C-NC-PadT7)") (class "Default")
      (node (ref "U4") (pin "T7") (pinfunction "NC_T7") (pintype "passive+no_connect"))
    )
    (net (code "104") (name "unconnected-(U5C-NC-PadJ1)") (class "Default")
      (node (ref "U5") (pin "J1") (pinfunction "NC_J1") (pintype "passive+no_connect"))
    )
    (net (code "105") (name "unconnected-(U5C-NC-PadJ9)") (class "Default")
      (node (ref "U5") (pin "J9") (pinfunction "NC_J9") (pintype "passive+no_connect"))
    )
    (net (code "106") (name "unconnected-(U5C-NC-PadL1)") (class "Default")
      (node (ref "U5") (pin "L1") (pinfunction "NC_L1") (pintype "passive+no_connect"))
    )
    (net (code "107") (name "unconnected-(U5C-NC-PadL9)") (class "Default")
      (node (ref "U5") (pin "L9") (pinfunction "NC_L9") (pintype "passive+no_connect"))
    )
    (net (code "108") (name "unconnected-(U5C-NC-PadM7)") (class "Default")
      (node (ref "U5") (pin "M7") (pinfunction "NC_M7") (pintype "passive+no_connect"))
    )
    (net (code "109") (name "unconnected-(U5C-NC-PadT3)") (class "Default")
      (node (ref "U5") (pin "T3") (pinfunction "NC_T3") (pintype "passive+no_connect"))
    )
    (net (code "110") (name "unconnected-(U5C-NC-PadT7)") (class "Default")
      (node (ref "U5") (pin "T7") (pinfunction "NC_T7") (pintype "passive+no_connect"))
    )
  )
)
